# Simple_EEM_Controller.net
KiCad netlist of a schematic drawn in Altium Designer
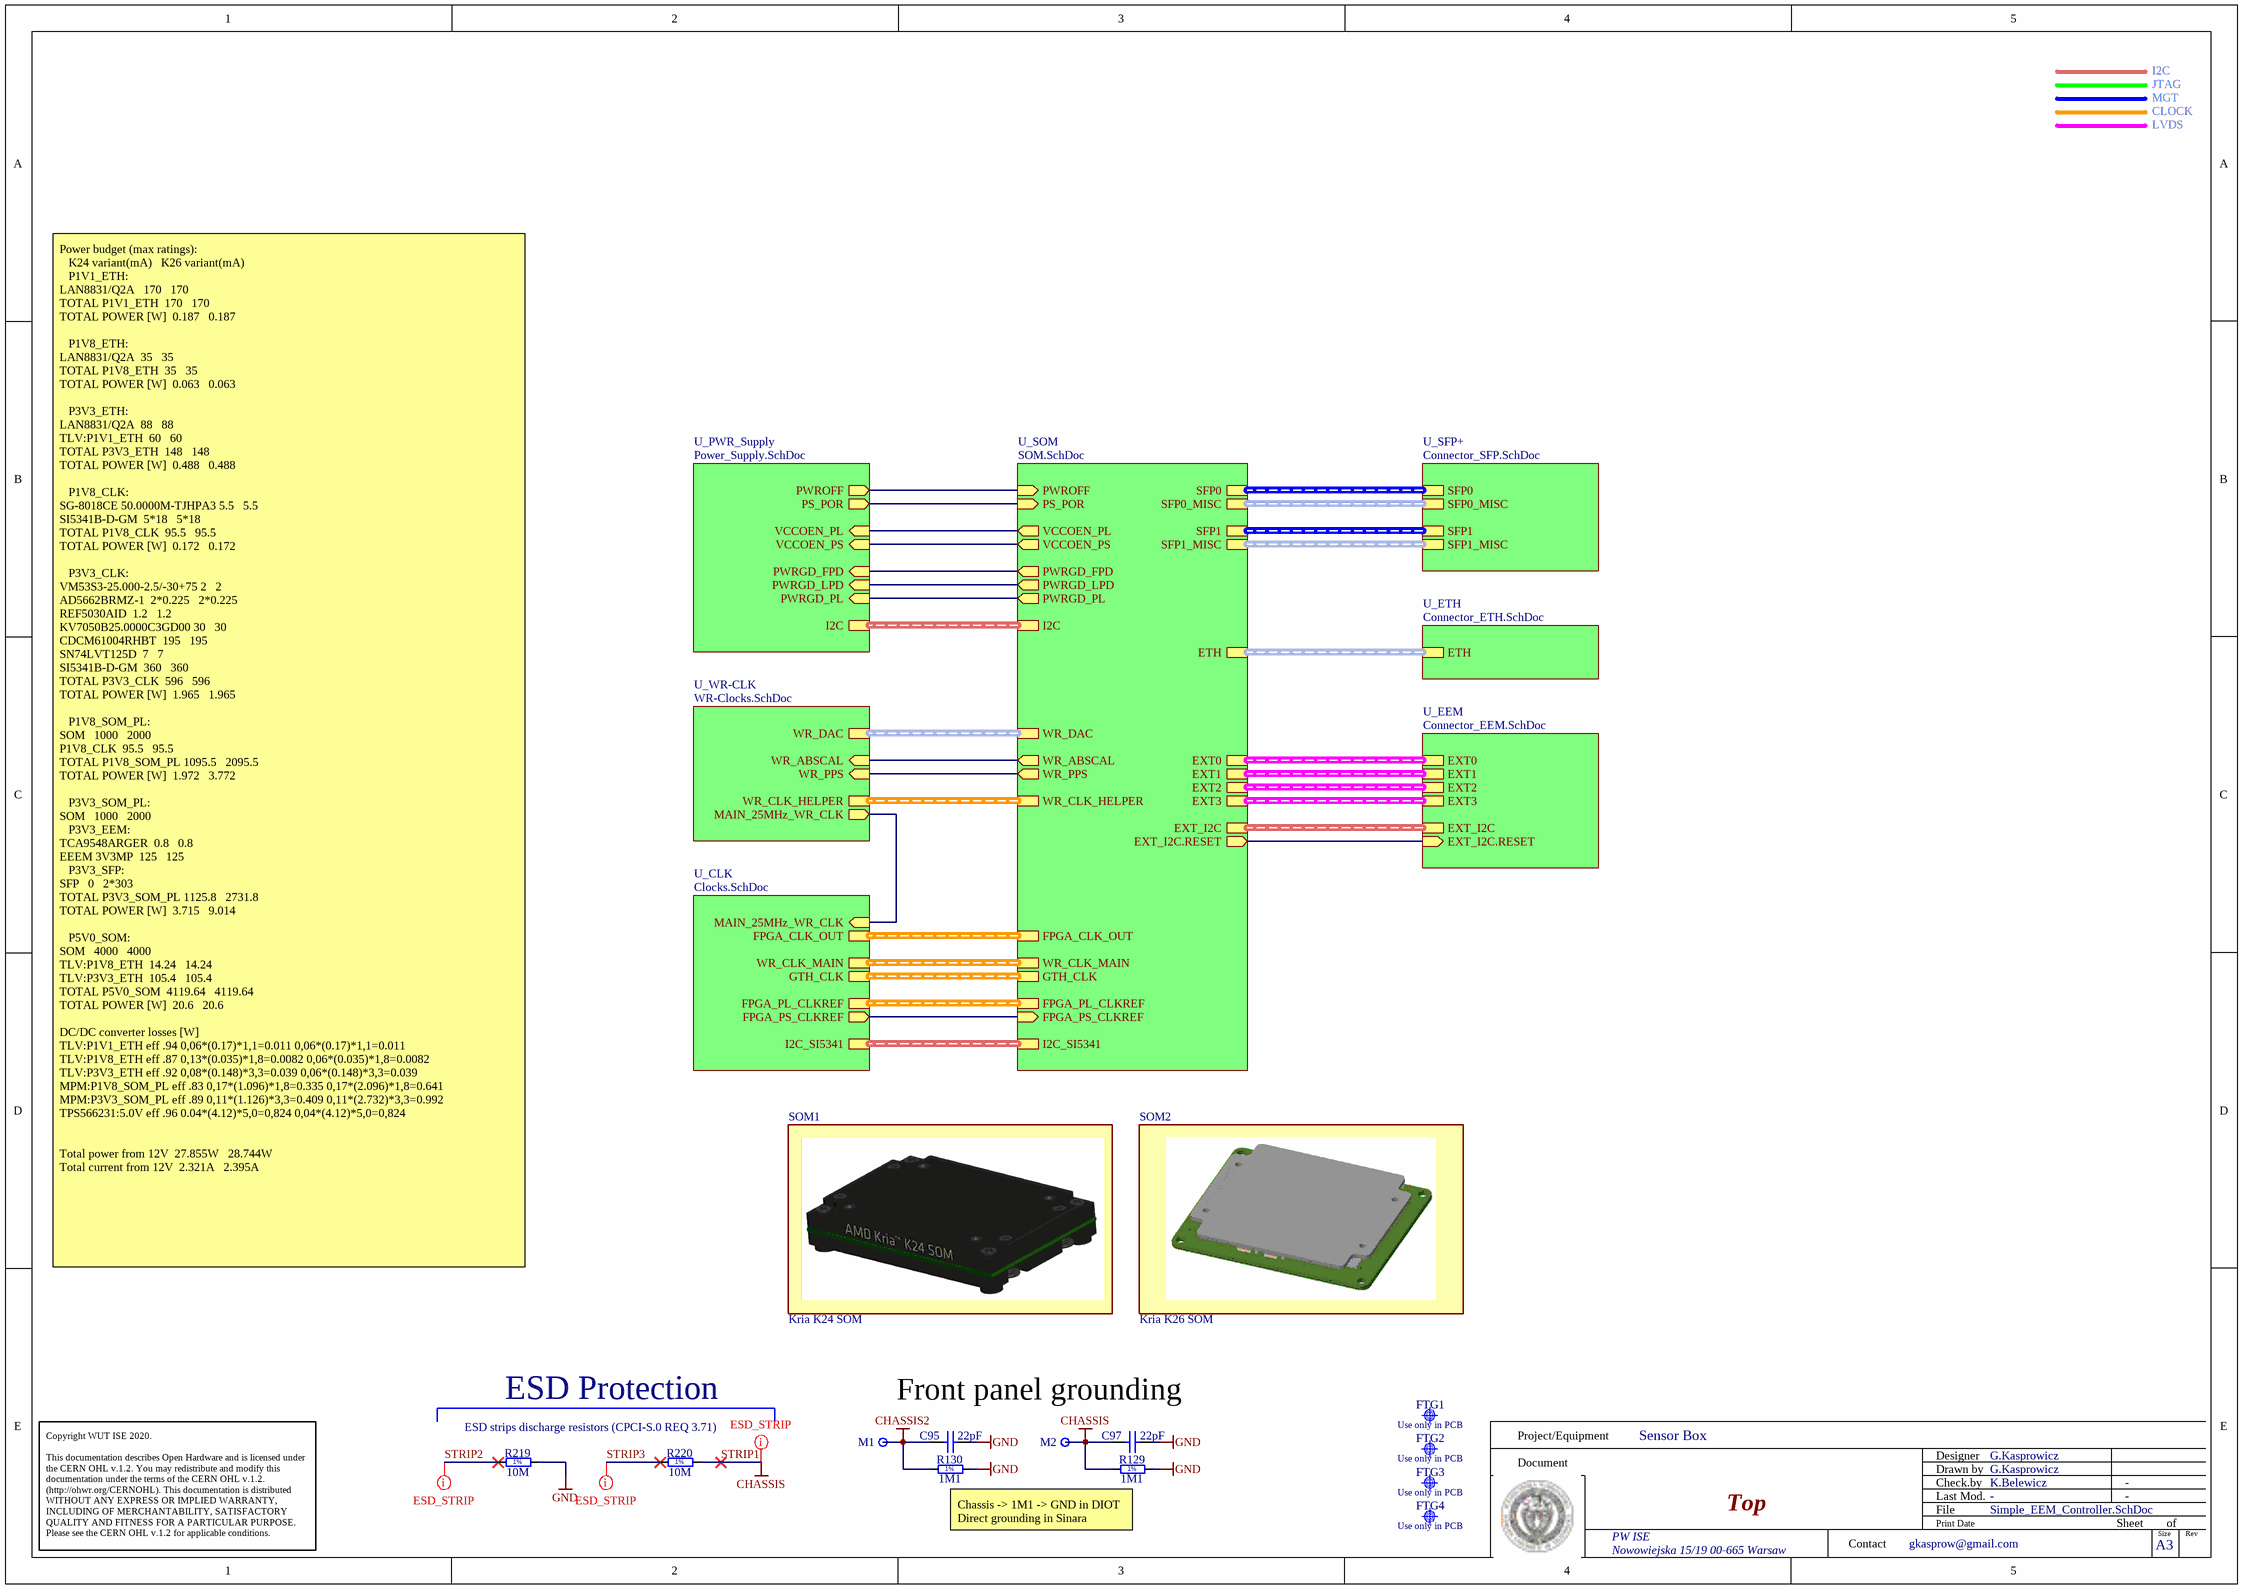
[diagram p0: Simple_EEM_Controller.SchDoc]

(export (version "E")
  (design (tool "Eeschema 10.0.6"))
  (components
    (comp (ref "C95")
      (value "22pF")
      (footprint "CAPC1005X55N")
      (description "Non-polarised capacitor")
      (fields
        (field (name "PART NUMBER") "CC0402_22PF_50V_5%_C0G")
        (field (name "VOLTAGE") "50V")
        (field (name "AUTHOR") "CERN DEM JLC")
      )
      (libsource (lib "Capacitors") (part "Capacitor - non polarized"))
    )
    (comp (ref "C97")
      (value "22pF")
      (footprint "CAPC1005X55N")
      (description "Non-polarised capacitor")
      (fields
        (field (name "PART NUMBER") "CC0402_22PF_50V_5%_C0G")
        (field (name "VOLTAGE") "50V")
        (field (name "AUTHOR") "CERN DEM JLC")
      )
      (libsource (lib "Capacitors") (part "Capacitor - non polarized"))
    )
    (comp (ref "FTG1")
      (value "Use only in PCB")
      (footprint "FIDUCIAL_TOP_C100-200")
      (description "Fiducial Target")
      (fields (field (name "PART NUMBER") "FIDUCIAL_TARGET_C100-200") (field (name "AUTHOR") "CERN DEM JLC"))
      (libsource (lib "Eletro-mechanical") (part "Fiducial Target"))
    )
    (comp (ref "FTG2")
      (value "Use only in PCB")
      (footprint "FIDUCIAL_TOP_S100-200")
      (description "Fiducial Target")
      (fields (field (name "PART NUMBER") "FIDUCIAL_TARGET_S100-200") (field (name "AUTHOR") "CERN DEM JLC"))
      (libsource (lib "Eletro-mechanical") (part "Fiducial Target"))
    )
    (comp (ref "FTG3")
      (value "Use only in PCB")
      (footprint "FIDUCIAL_TOP_S100-200")
      (description "Fiducial Target")
      (fields (field (name "PART NUMBER") "FIDUCIAL_TARGET_S100-200") (field (name "AUTHOR") "CERN DEM JLC"))
      (libsource (lib "Eletro-mechanical") (part "Fiducial Target"))
    )
    (comp (ref "FTG4")
      (value "Use only in PCB")
      (footprint "FIDUCIAL_TOP_S100-200")
      (description "Fiducial Target")
      (fields (field (name "PART NUMBER") "FIDUCIAL_TARGET_S100-200") (field (name "AUTHOR") "CERN DEM JLC"))
      (libsource (lib "Eletro-mechanical") (part "Fiducial Target"))
    )
    (comp (ref "M1")
      (value "Plated Hole")
      (footprint "MTG300_600")
      (description "Single Terminal Socket")
      (fields (field (name "PART NUMBER") "PLATED_HOLE3.0_PAD6.0") (field (name "AUTHOR") "CERN DEM JLC"))
      (libsource (lib "Eletro-mechanical") (part "Single Terminal Socket"))
    )
    (comp (ref "M2")
      (value "Plated Hole")
      (footprint "MTG300_600")
      (description "Single Terminal Socket")
      (fields (field (name "PART NUMBER") "PLATED_HOLE3.0_PAD6.0") (field (name "AUTHOR") "CERN DEM JLC"))
      (libsource (lib "Eletro-mechanical") (part "Single Terminal Socket"))
    )
    (comp (ref "R129")
      (value "1M1")
      (footprint "RESC2012X60N")
      (description "Resistor - 1%")
      (fields
        (field (name "PART NUMBER") "R0805_1M1_1%_0.125W_100PPM")
        (field (name "MANUFACTURER") "GENERIC")
        (field (name "AUTHOR") "CERN DEM JLC")
      )
      (libsource (lib "Resistors") (part "Resistor - 1%"))
    )
    (comp (ref "R130")
      (value "1M1")
      (footprint "RESC2012X60N")
      (description "Resistor - 1%")
      (fields
        (field (name "PART NUMBER") "R0805_1M1_1%_0.125W_100PPM")
        (field (name "MANUFACTURER") "GENERIC")
        (field (name "AUTHOR") "CERN DEM JLC")
      )
      (libsource (lib "Resistors") (part "Resistor - 1%"))
    )
    (comp (ref "R219")
      (value "10M")
      (footprint "RESC2113X55N")
      (description "Resistor - 1%")
      (fields
        (field (name "PART NUMBER") "R0805_10M_1%_0.125W_100PPM_VISHAY_CRCW e3")
        (field (name "POWER") "0.125W")
        (field (name "AUTHOR") "CERN DEM BC")
      )
      (libsource (lib "Resistors") (part "Resistor - 1%"))
    )
    (comp (ref "R220")
      (value "10M")
      (footprint "RESC2113X55N")
      (description "Resistor - 1%")
      (fields
        (field (name "PART NUMBER") "R0805_10M_1%_0.125W_100PPM_VISHAY_CRCW e3")
        (field (name "POWER") "0.125W")
        (field (name "AUTHOR") "CERN DEM BC")
      )
      (libsource (lib "Resistors") (part "Resistor - 1%"))
    )
    (comp (ref "SOM1")
      (value "Kria K24 SOM")
      (footprint "Kria K24 SOM")
      (fields (field (name "MANUFACTURER") "AMD"))
      (libsource (lib "Simple_EEM_Controller") (part "K24"))
    )
    (comp (ref "SOM2")
      (value "Kria K26 SOM")
      (footprint "Kria K26 SOM")
      (fields (field (name "MANUFACTURER") "AMD"))
      (libsource (lib "Simple_EEM_Controller") (part "K26"))
    )
  )
  (nets
    (net (code "25") (name "/STRIP2") (class "Default")
      (node (ref "R219") (pin "1") (pinfunction "1_1") (pintype "passive+no_connect"))
    )
    (net (code "26") (name "/STRIP3") (class "Default")
      (node (ref "R220") (pin "1") (pinfunction "1_1") (pintype "passive+no_connect"))
    )
    (net (code "34") (name "CHASSIS") (class "Default")
      (node (ref "C97") (pin "1") (pinfunction "1_1") (pintype "passive"))
      (node (ref "M2") (pin "1") (pinfunction "1_1") (pintype "bidirectional"))
      (node (ref "R129") (pin "1") (pinfunction "1_1") (pintype "passive"))
      (node (ref "R220") (pin "2") (pinfunction "2_2") (pintype "passive"))
    )
    (net (code "35") (name "CHASSIS2") (class "Default")
      (node (ref "C95") (pin "1") (pinfunction "1_1") (pintype "passive"))
      (node (ref "M1") (pin "1") (pinfunction "1_1") (pintype "bidirectional"))
      (node (ref "R130") (pin "1") (pinfunction "1_1") (pintype "passive"))
    )
    (net (code "36") (name "GND") (class "Default")
      (node (ref "C95") (pin "2") (pinfunction "2_2") (pintype "passive"))
      (node (ref "C97") (pin "2") (pinfunction "2_2") (pintype "passive"))
      (node (ref "R129") (pin "2") (pinfunction "2_2") (pintype "passive"))
      (node (ref "R130") (pin "2") (pinfunction "2_2") (pintype "passive"))
      (node (ref "R219") (pin "2") (pinfunction "2_2") (pintype "passive"))
    )
  )
)
